# Esp_sensor.net
KiCad netlist of a schematic drawn in EAGLE
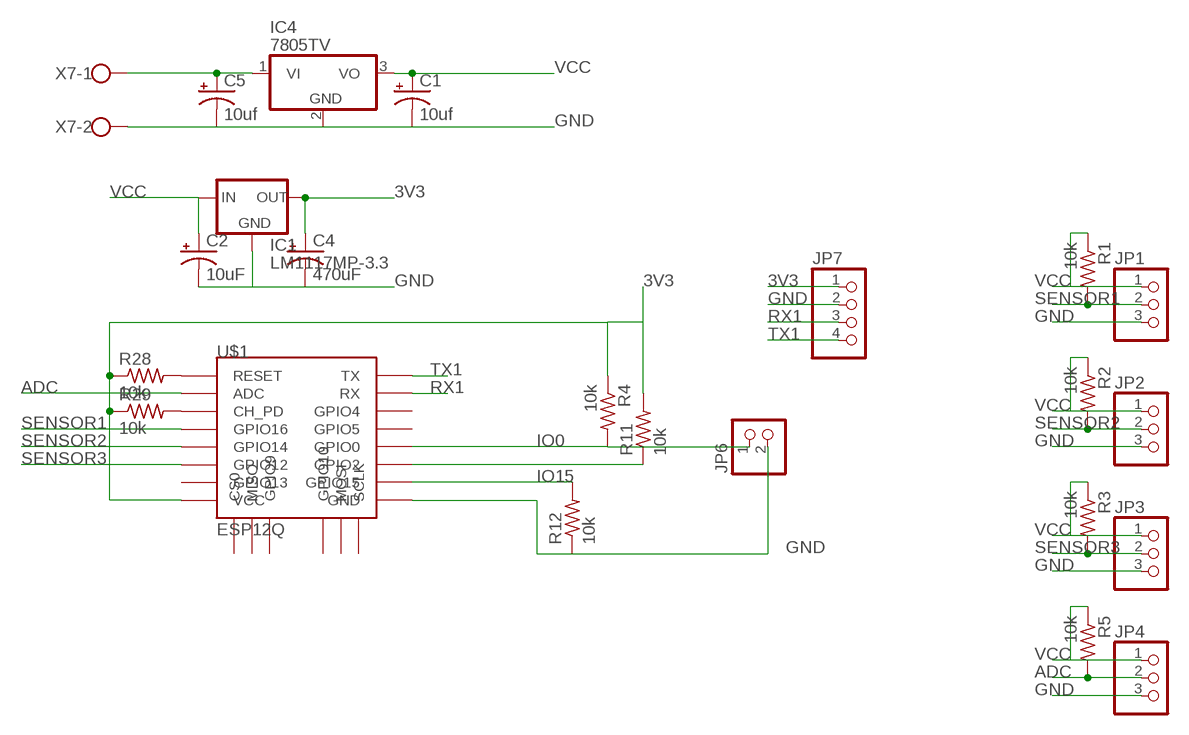
[diagram p0: schematic, sheet 1]

(export (version "E")
  (design (tool "Eeschema 10.0.6"))
  (components
    (comp (ref "C1")
      (value "10uf")
      (footprint "eagle-import:E2,5-6")
      (libsource (lib "eagle-import") (part "CPOL-USE2.5-6"))
    )
    (comp (ref "C2")
      (value "10uF")
      (footprint "eagle-import:E2,5-6")
      (libsource (lib "eagle-import") (part "CPOL-USE2.5-6"))
    )
    (comp (ref "C4")
      (value "470uF")
      (footprint "eagle-import:E5-8,5")
      (libsource (lib "eagle-import") (part "CPOL-USE5-8.5"))
    )
    (comp (ref "C5")
      (value "10uf")
      (footprint "eagle-import:E2,5-6")
      (libsource (lib "eagle-import") (part "CPOL-USE2.5-6"))
    )
    (comp (ref "IC1")
      (value "LM1117MP-3.3")
      (footprint "eagle-import:SOT223")
      (fields (field (name "MF") "Texas Instruments"))
      (libsource (lib "eagle-import") (part "LM1117?-MP3.3"))
    )
    (comp (ref "IC4")
      (value "7805TV")
      (footprint "eagle-import:TO220V")
      (libsource (lib "eagle-import") (part "78TV05"))
    )
    (comp (ref "JP1")
      (value "PINHD-1X3")
      (footprint "eagle-import:1X03")
      (libsource (lib "eagle-import") (part "PINHD-1X3"))
    )
    (comp (ref "JP2")
      (value "PINHD-1X3")
      (footprint "eagle-import:1X03")
      (libsource (lib "eagle-import") (part "PINHD-1X3"))
    )
    (comp (ref "JP3")
      (value "PINHD-1X3")
      (footprint "eagle-import:1X03")
      (libsource (lib "eagle-import") (part "PINHD-1X3"))
    )
    (comp (ref "JP4")
      (value "PINHD-1X3")
      (footprint "eagle-import:1X03")
      (libsource (lib "eagle-import") (part "PINHD-1X3"))
    )
    (comp (ref "JP6")
      (value "PINHD-1X2")
      (footprint "eagle-import:1X02")
      (libsource (lib "eagle-import") (part "PINHD-1X2"))
    )
    (comp (ref "JP7")
      (value "PINHD-1X4")
      (footprint "eagle-import:1X04")
      (libsource (lib "eagle-import") (part "PINHD-1X4"))
    )
    (comp (ref "R1")
      (value "10k")
      (footprint "eagle-import:0207_10")
      (libsource (lib "eagle-import") (part "R-US_0207/10"))
    )
    (comp (ref "R2")
      (value "10k")
      (footprint "eagle-import:0207_10")
      (libsource (lib "eagle-import") (part "R-US_0207/10"))
    )
    (comp (ref "R3")
      (value "10k")
      (footprint "eagle-import:0207_10")
      (libsource (lib "eagle-import") (part "R-US_0207/10"))
    )
    (comp (ref "R4")
      (value "10k")
      (footprint "eagle-import:0207_10")
      (libsource (lib "eagle-import") (part "R-US_0207/10"))
    )
    (comp (ref "R5")
      (value "10k")
      (footprint "eagle-import:0207_10")
      (libsource (lib "eagle-import") (part "R-US_0207/10"))
    )
    (comp (ref "R11")
      (value "10k")
      (footprint "eagle-import:0207_10")
      (libsource (lib "eagle-import") (part "R-US_0207/10"))
    )
    (comp (ref "R12")
      (value "10k")
      (footprint "eagle-import:0207_10")
      (libsource (lib "eagle-import") (part "R-US_0207/10"))
    )
    (comp (ref "R28")
      (value "10k")
      (footprint "eagle-import:0207_10")
      (libsource (lib "eagle-import") (part "R-US_0207/10"))
    )
    (comp (ref "R29")
      (value "10k")
      (footprint "eagle-import:0207_10")
      (libsource (lib "eagle-import") (part "R-US_0207/10"))
    )
    (comp (ref "U$1")
      (value "ESP12Q")
      (footprint "eagle-import:ESP12Q")
      (libsource (lib "eagle-import") (part "ESP12Q"))
    )
    (comp (ref "X7")
      (value "W237-102")
      (footprint "eagle-import:W237-102")
      (fields (field (name "MPN") "237-102"))
      (libsource (lib "eagle-import") (part "W237-102"))
    )
  )
  (nets
    (net (code "1") (name "/3V3") (class "Default")
      (node (ref "C4") (pin "+") (pinfunction "+_+") (pintype "passive"))
      (node (ref "IC1") (pin "2") (pinfunction "OUT_2") (pintype "passive"))
      (node (ref "IC1") (pin "4") (pinfunction "OUT_4") (pintype "passive"))
      (node (ref "JP7") (pin "1") (pinfunction "1_1") (pintype "passive"))
      (node (ref "R11") (pin "2") (pinfunction "2_2") (pintype "passive"))
      (node (ref "R28") (pin "1") (pinfunction "1_1") (pintype "passive"))
      (node (ref "R29") (pin "1") (pinfunction "1_1") (pintype "passive"))
      (node (ref "R4") (pin "1") (pinfunction "1_1") (pintype "passive"))
      (node (ref "U$1") (pin "VCC") (pinfunction "VCC_VCC") (pintype "bidirectional"))
    )
    (net (code "2") (name "/ADC") (class "Default")
      (node (ref "JP4") (pin "2") (pinfunction "2_2") (pintype "passive"))
      (node (ref "R5") (pin "2") (pinfunction "2_2") (pintype "passive"))
      (node (ref "U$1") (pin "ADC") (pinfunction "ADC_ADC") (pintype "bidirectional"))
    )
    (net (code "3") (name "/GND") (class "Default")
      (node (ref "C1") (pin "-") (pinfunction "-_-") (pintype "passive"))
      (node (ref "C2") (pin "-") (pinfunction "-_-") (pintype "passive"))
      (node (ref "C4") (pin "-") (pinfunction "-_-") (pintype "passive"))
      (node (ref "C5") (pin "-") (pinfunction "-_-") (pintype "passive"))
      (node (ref "IC1") (pin "1") (pinfunction "GND_1") (pintype "input"))
      (node (ref "IC4") (pin "2") (pinfunction "GND_2") (pintype "passive"))
      (node (ref "JP1") (pin "3") (pinfunction "3_3") (pintype "passive"))
      (node (ref "JP2") (pin "3") (pinfunction "3_3") (pintype "passive"))
      (node (ref "JP3") (pin "3") (pinfunction "3_3") (pintype "passive"))
      (node (ref "JP4") (pin "3") (pinfunction "3_3") (pintype "passive"))
      (node (ref "JP6") (pin "2") (pinfunction "2_2") (pintype "passive"))
      (node (ref "JP7") (pin "2") (pinfunction "2_2") (pintype "passive"))
      (node (ref "R12") (pin "1") (pinfunction "1_1") (pintype "passive"))
      (node (ref "U$1") (pin "GND") (pinfunction "GND_GND") (pintype "bidirectional"))
      (node (ref "X7") (pin "2") (pinfunction "KL_2") (pintype "passive"))
    )
    (net (code "4") (name "/IO0") (class "Default")
      (node (ref "JP6") (pin "1") (pinfunction "1_1") (pintype "passive"))
      (node (ref "R4") (pin "2") (pinfunction "2_2") (pintype "passive"))
      (node (ref "U$1") (pin "GPIO0") (pinfunction "GPIO0_GPIO0") (pintype "bidirectional"))
    )
    (net (code "5") (name "/IO15") (class "Default")
      (node (ref "R12") (pin "2") (pinfunction "2_2") (pintype "passive"))
      (node (ref "U$1") (pin "GPIO15") (pinfunction "GPIO15_GPIO15") (pintype "bidirectional"))
    )
    (net (code "6") (name "/RX1") (class "Default")
      (node (ref "JP7") (pin "3") (pinfunction "3_3") (pintype "passive"))
      (node (ref "U$1") (pin "RX") (pinfunction "RX_RX") (pintype "bidirectional"))
    )
    (net (code "7") (name "/SENSOR1") (class "Default")
      (node (ref "JP1") (pin "2") (pinfunction "2_2") (pintype "passive"))
      (node (ref "R1") (pin "2") (pinfunction "2_2") (pintype "passive"))
      (node (ref "U$1") (pin "GPIO16") (pinfunction "GPIO16_GPIO16") (pintype "bidirectional"))
    )
    (net (code "8") (name "/SENSOR2") (class "Default")
      (node (ref "JP2") (pin "2") (pinfunction "2_2") (pintype "passive"))
      (node (ref "R2") (pin "2") (pinfunction "2_2") (pintype "passive"))
      (node (ref "U$1") (pin "GPIO14") (pinfunction "GPIO14_GPIO14") (pintype "bidirectional"))
    )
    (net (code "9") (name "/SENSOR3") (class "Default")
      (node (ref "JP3") (pin "2") (pinfunction "2_2") (pintype "passive"))
      (node (ref "R3") (pin "2") (pinfunction "2_2") (pintype "passive"))
      (node (ref "U$1") (pin "GPIO12") (pinfunction "GPIO12_GPIO12") (pintype "bidirectional"))
    )
    (net (code "10") (name "/TX1") (class "Default")
      (node (ref "JP7") (pin "4") (pinfunction "4_4") (pintype "passive"))
      (node (ref "U$1") (pin "TX") (pinfunction "TX_TX") (pintype "bidirectional"))
    )
    (net (code "11") (name "/VCC") (class "Default")
      (node (ref "C1") (pin "+") (pinfunction "+_+") (pintype "passive"))
      (node (ref "C2") (pin "+") (pinfunction "+_+") (pintype "passive"))
      (node (ref "IC1") (pin "3") (pinfunction "IN_3") (pintype "input"))
      (node (ref "IC4") (pin "3") (pinfunction "VO_3") (pintype "passive"))
      (node (ref "JP1") (pin "1") (pinfunction "1_1") (pintype "passive"))
      (node (ref "JP2") (pin "1") (pinfunction "1_1") (pintype "passive"))
      (node (ref "JP3") (pin "1") (pinfunction "1_1") (pintype "passive"))
      (node (ref "JP4") (pin "1") (pinfunction "1_1") (pintype "passive"))
      (node (ref "R1") (pin "1") (pinfunction "1_1") (pintype "passive"))
      (node (ref "R2") (pin "1") (pinfunction "1_1") (pintype "passive"))
      (node (ref "R3") (pin "1") (pinfunction "1_1") (pintype "passive"))
      (node (ref "R5") (pin "1") (pinfunction "1_1") (pintype "passive"))
    )
    (net (code "12") (name "Net-(IC4-VI)") (class "Default")
      (node (ref "C5") (pin "+") (pinfunction "+_+") (pintype "passive"))
      (node (ref "IC4") (pin "1") (pinfunction "VI_1") (pintype "input"))
      (node (ref "X7") (pin "1") (pinfunction "KL_1") (pintype "passive"))
    )
    (net (code "13") (name "Net-(R11-Pad1)") (class "Default")
      (node (ref "R11") (pin "1") (pinfunction "1_1") (pintype "passive"))
      (node (ref "U$1") (pin "GPIO2") (pinfunction "GPIO2_GPIO2") (pintype "bidirectional"))
    )
    (net (code "14") (name "Net-(R28-Pad2)") (class "Default")
      (node (ref "R28") (pin "2") (pinfunction "2_2") (pintype "passive"))
      (node (ref "U$1") (pin "RESET") (pinfunction "RESET_RESET") (pintype "bidirectional"))
    )
    (net (code "15") (name "Net-(R29-Pad2)") (class "Default")
      (node (ref "R29") (pin "2") (pinfunction "2_2") (pintype "passive"))
      (node (ref "U$1") (pin "CH_PD") (pinfunction "CH_PD_CH_PD") (pintype "bidirectional"))
    )
    (net (code "16") (name "unconnected-(U$1-PadCS0)") (class "Default")
      (node (ref "U$1") (pin "CS0") (pinfunction "CS0_CS0") (pintype "bidirectional"))
    )
    (net (code "17") (name "unconnected-(U$1-PadGPIO4)") (class "Default")
      (node (ref "U$1") (pin "GPIO4") (pinfunction "GPIO4_GPIO4") (pintype "bidirectional"))
    )
    (net (code "18") (name "unconnected-(U$1-PadGPIO5)") (class "Default")
      (node (ref "U$1") (pin "GPIO5") (pinfunction "GPIO5_GPIO5") (pintype "bidirectional"))
    )
    (net (code "19") (name "unconnected-(U$1-PadGPIO9)") (class "Default")
      (node (ref "U$1") (pin "GPIO9") (pinfunction "GPIO9_GPIO9") (pintype "bidirectional"))
    )
    (net (code "20") (name "unconnected-(U$1-PadGPIO10)") (class "Default")
      (node (ref "U$1") (pin "GPIO10") (pinfunction "GPIO10_GPIO10") (pintype "bidirectional"))
    )
    (net (code "21") (name "unconnected-(U$1-PadGPIO13)") (class "Default")
      (node (ref "U$1") (pin "GPIO13") (pinfunction "GPIO13_GPIO13") (pintype "bidirectional"))
    )
    (net (code "22") (name "unconnected-(U$1-PadMISO)") (class "Default")
      (node (ref "U$1") (pin "MISO") (pinfunction "MISO_MISO") (pintype "bidirectional"))
    )
    (net (code "23") (name "unconnected-(U$1-PadMOSI)") (class "Default")
      (node (ref "U$1") (pin "MOSI") (pinfunction "MOSI_MOSI") (pintype "bidirectional"))
    )
    (net (code "24") (name "unconnected-(U$1-PadSCLK)") (class "Default")
      (node (ref "U$1") (pin "SCLK") (pinfunction "SCLK_SCLK") (pintype "bidirectional"))
    )
  )
)
